# 467999_001_3_4.net
KiCad netlist of a schematic drawn in Altium Designer
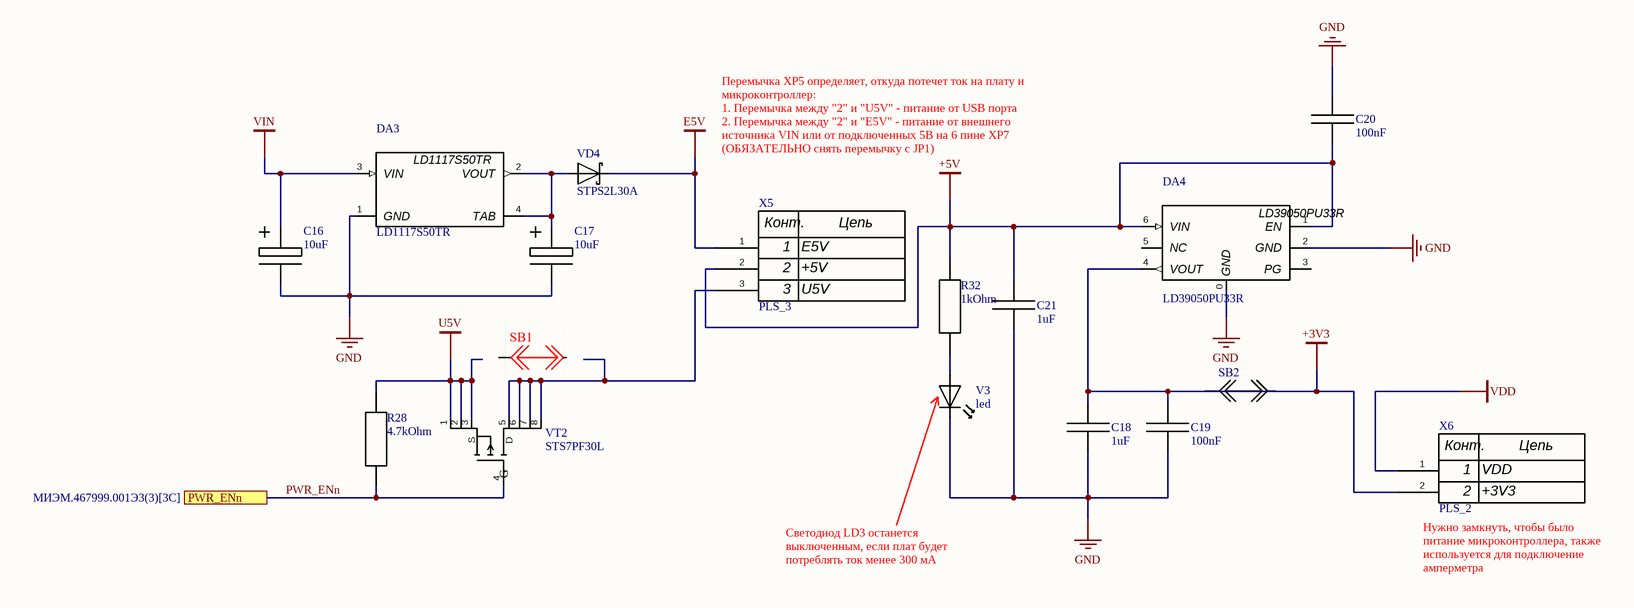
[diagram p0: МИЭМ.467999.001Э3(4).SchDoc]

(export (version "E")
  (design (tool "Eeschema 10.0.6"))
  (components
    (comp (ref "C16")
      (value "10uF")
      (footprint "TAJB106K025R")
      (fields
        (field (name "TOLERANCE") "10%")
        (field (name "PARTNUMBER") "TAJB106K025RNJ")
        (field (name "MANUFACTURER") "Kyocera AVX")
      )
      (libsource (lib "Capacitor_GOST") (part "Polarized Capacitor"))
    )
    (comp (ref "C17")
      (value "10uF")
      (footprint "TAJB106K025R")
      (fields
        (field (name "TOLERANCE") "10%")
        (field (name "PARTNUMBER") "TAJB106K025RNJ")
        (field (name "MANUFACTURER") "Kyocera AVX")
      )
      (libsource (lib "Capacitor_GOST") (part "Polarized Capacitor"))
    )
    (comp (ref "C18")
      (value "1uF")
      (footprint "0603")
      (fields
        (field (name "TOLERANCE") "10%")
        (field (name "PARTNUMBER") "GRM185R61A105K")
        (field (name "MANUFACTURER") "Murata Electronics")
      )
      (libsource (lib "Capacitor_GOST") (part "Сapacitor"))
    )
    (comp (ref "C19")
      (value "100nF")
      (footprint "0603")
      (fields
        (field (name "TOLERANCE") "10%")
        (field (name "PARTNUMBER") "CC0603KRX7R0BB104")
        (field (name "MANUFACTURER") "Yageo")
      )
      (libsource (lib "Capacitor_GOST") (part "Сapacitor"))
    )
    (comp (ref "C20")
      (value "100nF")
      (footprint "0603")
      (fields
        (field (name "TOLERANCE") "10%")
        (field (name "PARTNUMBER") "CC0603KRX7R0BB104")
        (field (name "MANUFACTURER") "Yageo")
      )
      (libsource (lib "Capacitor_GOST") (part "Сapacitor"))
    )
    (comp (ref "C21")
      (value "1uF")
      (footprint "0603")
      (fields
        (field (name "TOLERANCE") "10%")
        (field (name "PARTNUMBER") "GRM185R61A105K")
        (field (name "MANUFACTURER") "Murata Electronics")
      )
      (libsource (lib "Capacitor_GOST") (part "Сapacitor"))
    )
    (comp (ref "DA3")
      (value "LD1117S50TR")
      (footprint "LD1117S50TR (SOT-223)")
      (fields (field (name "MANUFACTURER") "STMicroelectronics"))
      (libsource (lib "ICs_GOST") (part "LD1117S50TR"))
    )
    (comp (ref "DA4")
      (value "LD39050PU33R")
      (footprint "LD39050PU33R (DFN6 (3x3 mm))")
      (fields (field (name "MANUFACTURER") "STMicroelectronics"))
      (libsource (lib "ICs_GOST") (part "LD39050PU33R"))
    )
    (comp (ref "R28")
      (value "4.7kOhm")
      (footprint "0603")
      (fields
        (field (name "POWER") "0.1Вт")
        (field (name "TOLERANCE") "5%")
        (field (name "PARTNUMBER") "RC0603JR-074K7L")
      )
      (libsource (lib "Resistor_GOST") (part "Resistor"))
    )
    (comp (ref "R32")
      (value "1kOhm")
      (footprint "0603")
      (fields
        (field (name "POWER") "0.1Вт")
        (field (name "TOLERANCE") "0.5%")
        (field (name "PARTNUMBER") "RP0603DRD071KL")
      )
      (libsource (lib "Resistor_GOST") (part "Resistor"))
    )
    (comp (ref "V3")
      (value "led")
      (footprint "FYLS-0603PGC")
      (fields
        (field (name "PARTNUMBER") "FYLS-0603PGC")
        (field (name "MANUFACTURER") "Ningbo Foryard Optoelectronics")
      )
      (libsource (lib "diodes_semiconductors_GOST") (part "led"))
    )
    (comp (ref "VD4")
      (value "STPS2L30A")
      (footprint "STPS2L30A")
      (fields (field (name "MANUFACTURER") "STMicroelectronics"))
      (libsource (lib "diodes_semiconductors_GOST") (part "STPS2L30A"))
    )
    (comp (ref "VT2")
      (value "STS7PF30L")
      (footprint "STS7PF30L")
      (fields (field (name "POWER") "2.5Вт") (field (name "MANUFACTURER") "STMicroelectronics"))
      (libsource (lib "diodes_semiconductors_GOST") (part "STS7PF30L"))
    )
    (comp (ref "X5") (value "PLS_3") (footprint "PLS_3") (libsource (lib "Connector_GOST") (part "PLS_3")))
    (comp (ref "X6") (value "PLS_2") (footprint "PLS_2") (libsource (lib "Connector_GOST") (part "PLS_2")))
  )
  (nets
    (net (code "1") (name "+3V3") (class "Default")
      (node (ref "C18") (pin "2") (pinfunction "2_2") (pintype "passive"))
      (node (ref "C19") (pin "2") (pinfunction "2_2") (pintype "passive"))
      (node (ref "DA4") (pin "4") (pinfunction "VOUT_4") (pintype "output"))
      (node (ref "X6") (pin "2") (pinfunction "2_2") (pintype "passive"))
    )
    (net (code "2") (name "+5V") (class "Default")
      (node (ref "C20") (pin "1") (pinfunction "1_1") (pintype "passive"))
      (node (ref "C21") (pin "2") (pinfunction "2_2") (pintype "passive"))
      (node (ref "DA4") (pin "1") (pinfunction "EN_1") (pintype "passive"))
      (node (ref "DA4") (pin "6") (pinfunction "VIN_6") (pintype "input"))
      (node (ref "R32") (pin "2") (pinfunction "2_2") (pintype "passive"))
      (node (ref "X5") (pin "2") (pinfunction "2_2") (pintype "passive"))
    )
    (net (code "3") (name "/PWR_ENn") (class "Default")
      (node (ref "R28") (pin "1") (pinfunction "1_1") (pintype "passive"))
      (node (ref "VT2") (pin "4") (pinfunction "G_4") (pintype "passive"))
    )
    (net (code "4") (name "E5V") (class "Default")
      (node (ref "VD4") (pin "1") (pinfunction "1_1") (pintype "passive"))
      (node (ref "X5") (pin "1") (pinfunction "1_1") (pintype "passive"))
    )
    (net (code "5") (name "GND") (class "Default")
      (node (ref "C16") (pin "2") (pinfunction "2_2") (pintype "passive"))
      (node (ref "C17") (pin "2") (pinfunction "2_2") (pintype "passive"))
      (node (ref "C18") (pin "1") (pinfunction "1_1") (pintype "passive"))
      (node (ref "C19") (pin "1") (pinfunction "1_1") (pintype "passive"))
      (node (ref "C20") (pin "2") (pinfunction "2_2") (pintype "passive"))
      (node (ref "C21") (pin "1") (pinfunction "1_1") (pintype "passive"))
      (node (ref "DA3") (pin "1") (pinfunction "GND_1") (pintype "passive"))
      (node (ref "DA4") (pin "0") (pinfunction "GND_0") (pintype "passive"))
      (node (ref "DA4") (pin "2") (pinfunction "GND_2") (pintype "passive"))
      (node (ref "V3") (pin "2") (pinfunction "2_2") (pintype "passive"))
    )
    (net (code "6") (name "Net-(DA3-TAB)") (class "Default")
      (node (ref "C17") (pin "1") (pinfunction "1_1") (pintype "passive"))
      (node (ref "DA3") (pin "2") (pinfunction "VOUT_2") (pintype "output"))
      (node (ref "DA3") (pin "4") (pinfunction "TAB_4") (pintype "passive"))
      (node (ref "VD4") (pin "2") (pinfunction "2_2") (pintype "passive"))
    )
    (net (code "7") (name "Net-(R32-Pad1)") (class "Default")
      (node (ref "R32") (pin "1") (pinfunction "1_1") (pintype "passive"))
      (node (ref "V3") (pin "1") (pinfunction "1_1") (pintype "passive"))
    )
    (net (code "8") (name "Net-(VT2-D-Pad5)") (class "Default")
      (node (ref "VT2") (pin "5") (pinfunction "D_5") (pintype "passive"))
      (node (ref "VT2") (pin "6") (pinfunction "D_6") (pintype "passive"))
      (node (ref "VT2") (pin "7") (pinfunction "D_7") (pintype "passive"))
      (node (ref "VT2") (pin "8") (pinfunction "D_8") (pintype "passive"))
      (node (ref "X5") (pin "3") (pinfunction "3_3") (pintype "passive"))
    )
    (net (code "9") (name "U5V") (class "Default")
      (node (ref "R28") (pin "2") (pinfunction "2_2") (pintype "passive"))
      (node (ref "VT2") (pin "1") (pinfunction "S_1") (pintype "passive"))
      (node (ref "VT2") (pin "2") (pinfunction "S_2") (pintype "passive"))
      (node (ref "VT2") (pin "3") (pinfunction "S_3") (pintype "passive"))
    )
    (net (code "10") (name "VDD") (class "Default")
      (node (ref "X6") (pin "1") (pinfunction "1_1") (pintype "passive"))
    )
    (net (code "11") (name "VIN") (class "Default")
      (node (ref "C16") (pin "1") (pinfunction "1_1") (pintype "passive"))
      (node (ref "DA3") (pin "3") (pinfunction "VIN_3") (pintype "input"))
    )
    (net (code "12") (name "unconnected-(DA4-NC-Pad5)") (class "Default")
      (node (ref "DA4") (pin "5") (pinfunction "NC_5") (pintype "passive"))
    )
    (net (code "13") (name "unconnected-(DA4-PG-Pad3)") (class "Default")
      (node (ref "DA4") (pin "3") (pinfunction "PG_3") (pintype "passive"))
    )
  )
)
